# Prototype_Board_bad_routing.net
KiCad netlist of a schematic drawn in EAGLE
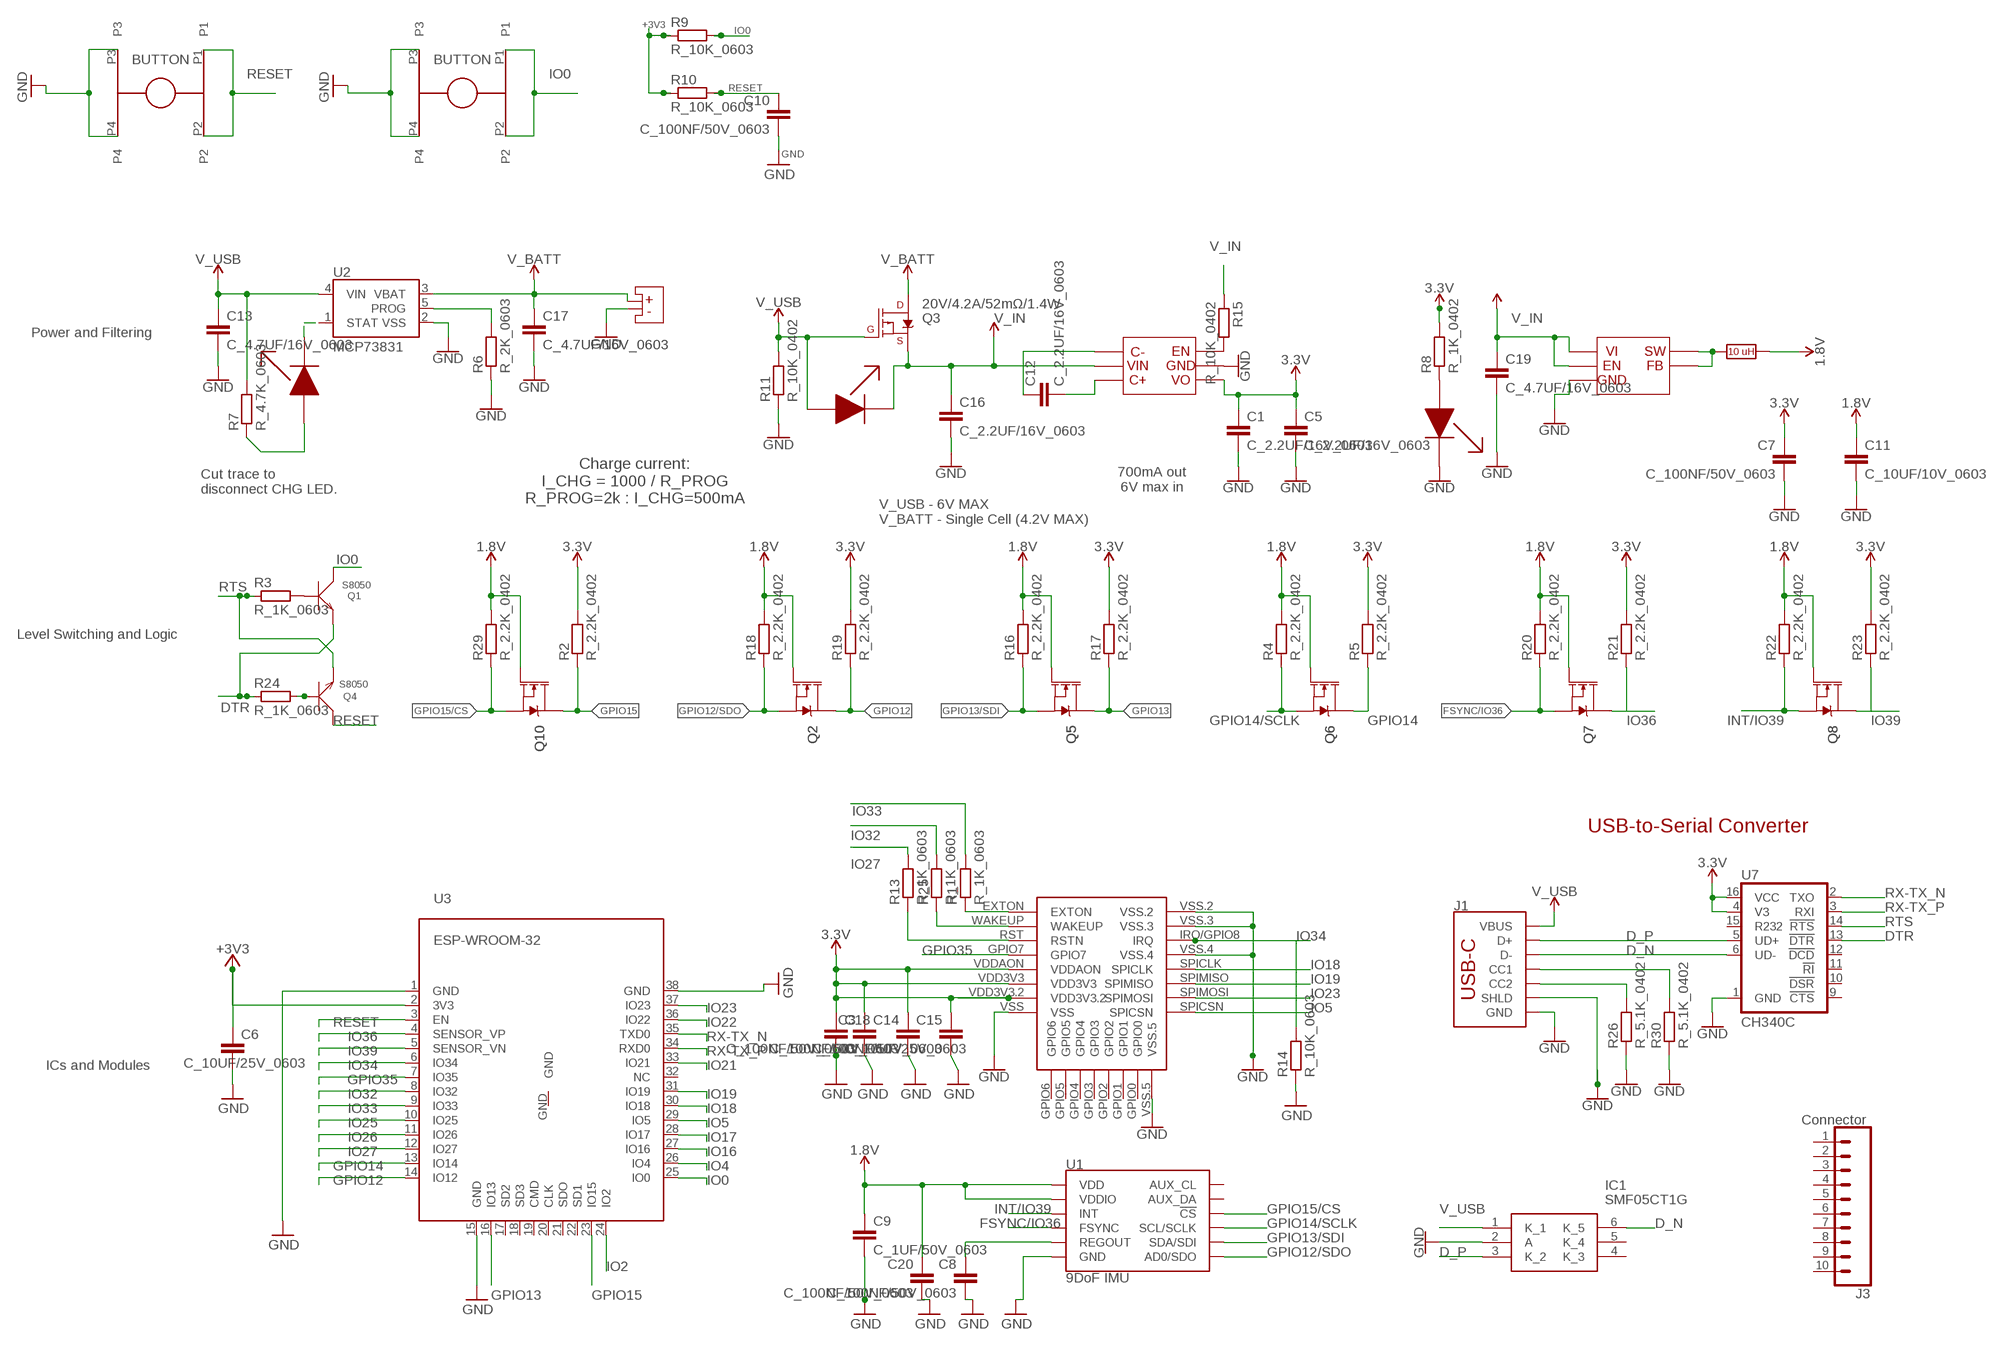
[diagram p0: schematic, sheet 1]

(export (version "E")
  (design (tool "Eeschema 10.0.6"))
  (components
    (comp (ref "C1")
      (value "C_2.2UF/16V_0603")
      (footprint "eagle-import:C0603")
      (fields (field (name "LCSC_PART") "C23630"))
      (libsource (lib "eagle-import") (part "C__06032.2UF/16V"))
    )
    (comp (ref "C3")
      (value "C_100NF/50V_0603")
      (footprint "eagle-import:C0603")
      (fields (field (name "LCSC_PART") "C14663"))
      (libsource (lib "eagle-import") (part "C__0603100NF/50V"))
    )
    (comp (ref "C5")
      (value "C_2.2UF/16V_0603")
      (footprint "eagle-import:C0603")
      (fields (field (name "LCSC_PART") "C23630"))
      (libsource (lib "eagle-import") (part "C__06032.2UF/16V"))
    )
    (comp (ref "C6")
      (value "C_10UF/25V_0603")
      (footprint "eagle-import:C0603")
      (fields (field (name "LCSC_PART") "C96446"))
      (libsource (lib "eagle-import") (part "C__060310UF/25V"))
    )
    (comp (ref "C7")
      (value "C_100NF/50V_0603")
      (footprint "eagle-import:C0603")
      (fields (field (name "LCSC_PART") "C14663"))
      (libsource (lib "eagle-import") (part "C__0603100NF/50V"))
    )
    (comp (ref "C8")
      (value "C_100NF/50V_0603")
      (footprint "eagle-import:C0603")
      (fields (field (name "LCSC_PART") "C14663"))
      (libsource (lib "eagle-import") (part "C__0603100NF/50V"))
    )
    (comp (ref "C9")
      (value "C_1UF/50V_0603")
      (footprint "eagle-import:C0603")
      (fields (field (name "LCSC_PART") "C15849"))
      (libsource (lib "eagle-import") (part "C__06031UF/50V"))
    )
    (comp (ref "C10")
      (value "C_100NF/50V_0603")
      (footprint "eagle-import:C0603")
      (fields (field (name "LCSC_PART") "C14663"))
      (libsource (lib "eagle-import") (part "C__0603100NF/50V"))
    )
    (comp (ref "C11")
      (value "C_10UF/10V_0603")
      (footprint "eagle-import:C0603")
      (fields (field (name "LCSC_PART") "C19702"))
      (libsource (lib "eagle-import") (part "C__060310UF/10V"))
    )
    (comp (ref "C12")
      (value "C_2.2UF/16V_0603")
      (footprint "eagle-import:C0603")
      (fields (field (name "LCSC_PART") "C23630"))
      (libsource (lib "eagle-import") (part "C__06032.2UF/16V"))
    )
    (comp (ref "C13")
      (value "C_4.7UF/16V_0603")
      (footprint "eagle-import:C0603")
      (fields (field (name "LCSC_PART") "C19666"))
      (libsource (lib "eagle-import") (part "C__06034.7UF/16V"))
    )
    (comp (ref "C14")
      (value "C_100NF/50V_0603")
      (footprint "eagle-import:C0603")
      (fields (field (name "LCSC_PART") "C14663"))
      (libsource (lib "eagle-import") (part "C__0603100NF/50V"))
    )
    (comp (ref "C15")
      (value "C_100NF/50V_0603")
      (footprint "eagle-import:C0603")
      (fields (field (name "LCSC_PART") "C14663"))
      (libsource (lib "eagle-import") (part "C__0603100NF/50V"))
    )
    (comp (ref "C16")
      (value "C_2.2UF/16V_0603")
      (footprint "eagle-import:C0603")
      (fields (field (name "LCSC_PART") "C23630"))
      (libsource (lib "eagle-import") (part "C__06032.2UF/16V"))
    )
    (comp (ref "C17")
      (value "C_4.7UF/16V_0603")
      (footprint "eagle-import:C0603")
      (fields (field (name "LCSC_PART") "C19666"))
      (libsource (lib "eagle-import") (part "C__06034.7UF/16V"))
    )
    (comp (ref "C18")
      (value "C_10UF/25V_0603")
      (footprint "eagle-import:C0603")
      (fields (field (name "LCSC_PART") "C96446"))
      (libsource (lib "eagle-import") (part "C__060310UF/25V"))
    )
    (comp (ref "C19")
      (value "C_4.7UF/16V_0603")
      (footprint "eagle-import:C0603")
      (fields (field (name "LCSC_PART") "C19666"))
      (libsource (lib "eagle-import") (part "C__06034.7UF/16V"))
    )
    (comp (ref "C20")
      (value "C_100NF/50V_0603")
      (footprint "eagle-import:C0603")
      (fields (field (name "LCSC_PART") "C14663"))
      (libsource (lib "eagle-import") (part "C__0603100NF/50V"))
    )
    (comp (ref "IC1")
      (value "SMF05CT1G")
      (footprint "eagle-import:SOT65P210X110-6N")
      (fields (field (name "MOUSER_PART_NUMBER") "863-SMF05CT1G"))
      (libsource (lib "eagle-import") (part "SMF05CT1G"))
    )
    (comp (ref "J1")
      (value "USB Type C")
      (footprint "eagle-import:USB-C-16P-2LAYER-PADS")
      (libsource (lib "eagle-import") (part "USB_C_2-LAYER_PADS"))
    )
    (comp (ref "J3")
      (value "Connector")
      (footprint "eagle-import:1X10")
      (libsource (lib "eagle-import") (part "CONN_10{dblquote}"))
    )
    (comp (ref "Q1")
      (value "S8050")
      (footprint "eagle-import:SOT23")
      (libsource (lib "eagle-import") (part "TRANSISTOR-NPN-SOT23"))
    )
    (comp (ref "Q2")
      (value "20V/0.2A/8MHz/1.2Ω/1Vth")
      (footprint "eagle-import:SOT-416FL")
      (libsource (lib "eagle-import") (part "MOSFET-NCH-RE1C002UN"))
    )
    (comp (ref "Q3")
      (value "20V/4.2A/52mΩ/1.4W")
      (footprint "eagle-import:SOT23-3@1")
      (libsource (lib "eagle-import") (part "MOSFET_PCH-DMG2305UX-7"))
    )
    (comp (ref "Q4")
      (value "S8050")
      (footprint "eagle-import:SOT23")
      (libsource (lib "eagle-import") (part "TRANSISTOR-NPN-SOT23"))
    )
    (comp (ref "Q5")
      (value "20V/0.2A/8MHz/1.2Ω/1Vth")
      (footprint "eagle-import:SOT-416FL")
      (libsource (lib "eagle-import") (part "MOSFET-NCH-RE1C002UN"))
    )
    (comp (ref "Q6")
      (value "20V/0.2A/8MHz/1.2Ω/1Vth")
      (footprint "eagle-import:SOT-416FL")
      (libsource (lib "eagle-import") (part "MOSFET-NCH-RE1C002UN"))
    )
    (comp (ref "Q7")
      (value "20V/0.2A/8MHz/1.2Ω/1Vth")
      (footprint "eagle-import:SOT-416FL")
      (libsource (lib "eagle-import") (part "MOSFET-NCH-RE1C002UN"))
    )
    (comp (ref "Q8")
      (value "20V/0.2A/8MHz/1.2Ω/1Vth")
      (footprint "eagle-import:SOT-416FL")
      (libsource (lib "eagle-import") (part "MOSFET-NCH-RE1C002UN"))
    )
    (comp (ref "Q10")
      (value "20V/0.2A/8MHz/1.2Ω/1Vth")
      (footprint "eagle-import:SOT-416FL")
      (libsource (lib "eagle-import") (part "MOSFET-NCH-RE1C002UN"))
    )
    (comp (ref "R1")
      (value "R_1K_0603")
      (footprint "eagle-import:R0603")
      (fields (field (name "LCSC_PART") "C21190"))
      (libsource (lib "eagle-import") (part "R__06031K"))
    )
    (comp (ref "R2")
      (value "R_2.2K_0402")
      (footprint "eagle-import:R0402")
      (fields (field (name "LCSC_PART") "C25879"))
      (libsource (lib "eagle-import") (part "R__04022.2K"))
    )
    (comp (ref "R3")
      (value "R_1K_0603")
      (footprint "eagle-import:R0603")
      (fields (field (name "LCSC_PART") "C21190"))
      (libsource (lib "eagle-import") (part "R__06031K"))
    )
    (comp (ref "R4")
      (value "R_2.2K_0402")
      (footprint "eagle-import:R0402")
      (fields (field (name "LCSC_PART") "C25879"))
      (libsource (lib "eagle-import") (part "R__04022.2K"))
    )
    (comp (ref "R5")
      (value "R_2.2K_0402")
      (footprint "eagle-import:R0402")
      (fields (field (name "LCSC_PART") "C25879"))
      (libsource (lib "eagle-import") (part "R__04022.2K"))
    )
    (comp (ref "R6")
      (value "R_2K_0603")
      (footprint "eagle-import:R0603")
      (fields (field (name "LCSC_PART") "C22975"))
      (libsource (lib "eagle-import") (part "R__06032K"))
    )
    (comp (ref "R7")
      (value "R_4.7K_0603")
      (footprint "eagle-import:R0603")
      (fields (field (name "LCSC_PART") "C23162"))
      (libsource (lib "eagle-import") (part "R__06034.7K"))
    )
    (comp (ref "R8")
      (value "R_1K_0402")
      (footprint "eagle-import:R0402")
      (fields (field (name "LCSC_PART") "C11702"))
      (libsource (lib "eagle-import") (part "R__04021K"))
    )
    (comp (ref "R9")
      (value "R_10K_0603")
      (footprint "eagle-import:R0603")
      (fields (field (name "LCSC_PART") "C25804"))
      (libsource (lib "eagle-import") (part "R__060310K"))
    )
    (comp (ref "R10")
      (value "R_10K_0603")
      (footprint "eagle-import:R0603")
      (fields (field (name "LCSC_PART") "C25804"))
      (libsource (lib "eagle-import") (part "R__060310K"))
    )
    (comp (ref "R11")
      (value "R_10K_0402")
      (footprint "eagle-import:R0402")
      (fields (field (name "LCSC_PART") "C25744"))
      (libsource (lib "eagle-import") (part "R__040210K"))
    )
    (comp (ref "R13")
      (value "R_1K_0603")
      (footprint "eagle-import:R0603")
      (fields (field (name "LCSC_PART") "C21190"))
      (libsource (lib "eagle-import") (part "R__06031K"))
    )
    (comp (ref "R14")
      (value "R_10K_0603")
      (footprint "eagle-import:R0603")
      (fields (field (name "LCSC_PART") "C25804"))
      (libsource (lib "eagle-import") (part "R__060310K"))
    )
    (comp (ref "R15")
      (value "R_10K_0402")
      (footprint "eagle-import:R0402")
      (fields (field (name "LCSC_PART") "C25744"))
      (libsource (lib "eagle-import") (part "R__040210K"))
    )
    (comp (ref "R16")
      (value "R_2.2K_0402")
      (footprint "eagle-import:R0402")
      (fields (field (name "LCSC_PART") "C25879"))
      (libsource (lib "eagle-import") (part "R__04022.2K"))
    )
    (comp (ref "R17")
      (value "R_2.2K_0402")
      (footprint "eagle-import:R0402")
      (fields (field (name "LCSC_PART") "C25879"))
      (libsource (lib "eagle-import") (part "R__04022.2K"))
    )
    (comp (ref "R18")
      (value "R_2.2K_0402")
      (footprint "eagle-import:R0402")
      (fields (field (name "LCSC_PART") "C25879"))
      (libsource (lib "eagle-import") (part "R__04022.2K"))
    )
    (comp (ref "R19")
      (value "R_2.2K_0402")
      (footprint "eagle-import:R0402")
      (fields (field (name "LCSC_PART") "C25879"))
      (libsource (lib "eagle-import") (part "R__04022.2K"))
    )
    (comp (ref "R20")
      (value "R_2.2K_0402")
      (footprint "eagle-import:R0402")
      (fields (field (name "LCSC_PART") "C25879"))
      (libsource (lib "eagle-import") (part "R__04022.2K"))
    )
    (comp (ref "R21")
      (value "R_2.2K_0402")
      (footprint "eagle-import:R0402")
      (fields (field (name "LCSC_PART") "C25879"))
      (libsource (lib "eagle-import") (part "R__04022.2K"))
    )
    (comp (ref "R22")
      (value "R_2.2K_0402")
      (footprint "eagle-import:R0402")
      (fields (field (name "LCSC_PART") "C25879"))
      (libsource (lib "eagle-import") (part "R__04022.2K"))
    )
    (comp (ref "R23")
      (value "R_2.2K_0402")
      (footprint "eagle-import:R0402")
      (fields (field (name "LCSC_PART") "C25879"))
      (libsource (lib "eagle-import") (part "R__04022.2K"))
    )
    (comp (ref "R24")
      (value "R_1K_0603")
      (footprint "eagle-import:R0603")
      (fields (field (name "LCSC_PART") "C21190"))
      (libsource (lib "eagle-import") (part "R__06031K"))
    )
    (comp (ref "R25")
      (value "R_1K_0603")
      (footprint "eagle-import:R0603")
      (fields (field (name "LCSC_PART") "C21190"))
      (libsource (lib "eagle-import") (part "R__06031K"))
    )
    (comp (ref "R26")
      (value "R_5.1K_0402")
      (footprint "eagle-import:R0402")
      (fields (field (name "LCSC_PART") "C25905"))
      (libsource (lib "eagle-import") (part "R__04025.1K"))
    )
    (comp (ref "R29")
      (value "R_2.2K_0402")
      (footprint "eagle-import:R0402")
      (fields (field (name "LCSC_PART") "C25879"))
      (libsource (lib "eagle-import") (part "R__04022.2K"))
    )
    (comp (ref "R30")
      (value "R_5.1K_0402")
      (footprint "eagle-import:R0402")
      (fields (field (name "LCSC_PART") "C25905"))
      (libsource (lib "eagle-import") (part "R__04025.1K"))
    )
    (comp (ref "U$1")
      (value "K2-6639SP-C4SC-04_C83206")
      (footprint "eagle-import:K2-6639SP-C4SC-04")
      (libsource (lib "eagle-import") (part "K2-6639SP-C4SC-04_C83206"))
    )
    (comp (ref "U$2")
      (value "MLF2012")
      (footprint "eagle-import:MLF2012")
      (libsource (lib "eagle-import") (part "MLF2012"))
    )
    (comp (ref "U$3")
      (value "K2-6639SP-C4SC-04_C83206")
      (footprint "eagle-import:K2-6639SP-C4SC-04")
      (libsource (lib "eagle-import") (part "K2-6639SP-C4SC-04_C83206"))
    )
    (comp (ref "U$4")
      (value "TPS62202DBVR")
      (footprint "eagle-import:TPS62202DBVR")
      (libsource (lib "eagle-import") (part "TPS62202DBVR"))
    )
    (comp (ref "U$5")
      (value "HE9008M6R")
      (footprint "eagle-import:HE9008M6R")
      (libsource (lib "eagle-import") (part "HE9008M6R"))
    )
    (comp (ref "U$6")
      (value "19-217/GHC-YR1S2/3T")
      (footprint "eagle-import:19-217_GHC-YR1S2_3T")
      (libsource (lib "eagle-import") (part "19-217/GHC-YR1S2/3T"))
    )
    (comp (ref "U$7")
      (value "19-217/GHC-YR1S2/3T")
      (footprint "eagle-import:19-217_GHC-YR1S2_3T")
      (libsource (lib "eagle-import") (part "19-217/GHC-YR1S2/3T"))
    )
    (comp (ref "U$8")
      (value "SM02B_PASS_TB_LF")
      (footprint "eagle-import:SM02B_PASS_TB_LF")
      (libsource (lib "eagle-import") (part "SM02B_PASS_TB_LF"))
    )
    (comp (ref "U$9")
      (value "19-217/GHC-YR1S2/3T")
      (footprint "eagle-import:19-217_GHC-YR1S2_3T")
      (libsource (lib "eagle-import") (part "19-217/GHC-YR1S2/3T"))
    )
    (comp (ref "U1")
      (value "9DoF IMU")
      (footprint "eagle-import:QFN24-3X3")
      (libsource (lib "eagle-import") (part "ICM-20948"))
    )
    (comp (ref "U2")
      (value "MCP73831")
      (footprint "eagle-import:SOT23-5")
      (libsource (lib "eagle-import") (part "MCP73831"))
    )
    (comp (ref "U3")
      (value "ESP-WROOM-32")
      (footprint "eagle-import:ESP-WROOM-32")
      (libsource (lib "eagle-import") (part "ESP-WROOM-32"))
    )
    (comp (ref "U5")
      (value "DWM1000")
      (footprint "eagle-import:DWM1000")
      (libsource (lib "eagle-import") (part "DWM1000"))
    )
    (comp (ref "U7")
      (value "CH340C")
      (footprint "eagle-import:SO016")
      (libsource (lib "eagle-import") (part "CH340C"))
    )
  )
  (nets
    (net (code "1") (name "+3V3") (class "Default")
      (node (ref "C6") (pin "1") (pinfunction "1_1") (pintype "passive"))
      (node (ref "R10") (pin "1") (pinfunction "1_1") (pintype "passive"))
      (node (ref "R9") (pin "1") (pinfunction "1_1") (pintype "passive"))
      (node (ref "U3") (pin "2") (pinfunction "3V3_2") (pintype "bidirectional"))
    )
    (net (code "2") (name "/DTR") (class "Default")
      (node (ref "Q1") (pin "2") (pinfunction "E_2") (pintype "passive"))
      (node (ref "R24") (pin "1") (pinfunction "1_1") (pintype "passive"))
      (node (ref "U7") (pin "13") (pinfunction "~{DTR}_13") (pintype "bidirectional"))
    )
    (net (code "3") (name "/D_N") (class "Default")
      (node (ref "IC1") (pin "6") (pinfunction "K_5_6") (pintype "bidirectional"))
      (node (ref "J1") (pin "A7") (pinfunction "D-_A7") (pintype "bidirectional"))
      (node (ref "J1") (pin "B7") (pinfunction "D-_B7") (pintype "bidirectional"))
      (node (ref "U7") (pin "6") (pinfunction "UD-_6") (pintype "bidirectional"))
    )
    (net (code "4") (name "/D_P") (class "Default")
      (node (ref "IC1") (pin "3") (pinfunction "K_2_3") (pintype "bidirectional"))
      (node (ref "J1") (pin "A6") (pinfunction "D+_A6") (pintype "bidirectional"))
      (node (ref "J1") (pin "B6") (pinfunction "D+_B6") (pintype "bidirectional"))
      (node (ref "U7") (pin "5") (pinfunction "UD+_5") (pintype "bidirectional"))
    )
    (net (code "5") (name "/GPIO14") (class "Default")
      (node (ref "Q6") (pin "3") (pinfunction "D_3") (pintype "bidirectional"))
      (node (ref "R5") (pin "1") (pinfunction "1_1") (pintype "passive"))
      (node (ref "U3") (pin "13") (pinfunction "IO14_13") (pintype "bidirectional"))
    )
    (net (code "6") (name "/GPIO14{slash}SCLK") (class "Default")
      (node (ref "Q6") (pin "2") (pinfunction "S_2") (pintype "bidirectional"))
      (node (ref "R4") (pin "1") (pinfunction "1_1") (pintype "passive"))
      (node (ref "U1") (pin "23") (pinfunction "SCL/SCLK_23") (pintype "bidirectional"))
    )
    (net (code "7") (name "/GPIO35") (class "Default")
      (node (ref "U3") (pin "7") (pinfunction "IO35_7") (pintype "bidirectional"))
      (node (ref "U5") (pin "GPIO7") (pinfunction "GPIO7_GPIO7") (pintype "bidirectional"))
    )
    (net (code "8") (name "/INT{slash}IO39") (class "Default")
      (node (ref "Q8") (pin "2") (pinfunction "S_2") (pintype "bidirectional"))
      (node (ref "R22") (pin "1") (pinfunction "1_1") (pintype "passive"))
      (node (ref "U1") (pin "12") (pinfunction "INT_12") (pintype "bidirectional"))
    )
    (net (code "9") (name "/IO0") (class "Default")
      (node (ref "Q1") (pin "3") (pinfunction "C_3") (pintype "passive"))
      (node (ref "R9") (pin "2") (pinfunction "2_2") (pintype "passive"))
      (node (ref "U$3") (pin "P1") (pinfunction "P1_P1") (pintype "bidirectional"))
      (node (ref "U$3") (pin "P2") (pinfunction "P2_P2") (pintype "bidirectional"))
      (node (ref "U3") (pin "25") (pinfunction "IO0_25") (pintype "bidirectional"))
    )
    (net (code "10") (name "/IO2") (class "Default")
      (node (ref "U3") (pin "24") (pinfunction "IO2_24") (pintype "bidirectional"))
    )
    (net (code "11") (name "/IO4") (class "Default")
      (node (ref "U3") (pin "26") (pinfunction "IO4_26") (pintype "bidirectional"))
    )
    (net (code "12") (name "/IO5") (class "Default")
      (node (ref "U3") (pin "29") (pinfunction "IO5_29") (pintype "bidirectional"))
      (node (ref "U5") (pin "SPICSN") (pinfunction "SPICSN_SPICSN") (pintype "bidirectional"))
    )
    (net (code "13") (name "/IO16") (class "Default")
      (node (ref "U3") (pin "27") (pinfunction "IO16_27") (pintype "bidirectional"))
    )
    (net (code "14") (name "/IO17") (class "Default")
      (node (ref "U3") (pin "28") (pinfunction "IO17_28") (pintype "bidirectional"))
    )
    (net (code "15") (name "/IO18") (class "Default")
      (node (ref "U3") (pin "30") (pinfunction "IO18_30") (pintype "bidirectional"))
      (node (ref "U5") (pin "SPICLK") (pinfunction "SPICLK_SPICLK") (pintype "bidirectional"))
    )
    (net (code "16") (name "/IO19") (class "Default")
      (node (ref "U3") (pin "31") (pinfunction "IO19_31") (pintype "bidirectional"))
      (node (ref "U5") (pin "SPIMISO") (pinfunction "SPIMISO_SPIMISO") (pintype "bidirectional"))
    )
    (net (code "17") (name "/IO21") (class "Default")
      (node (ref "U3") (pin "33") (pinfunction "IO21_33") (pintype "bidirectional"))
    )
    (net (code "18") (name "/IO22") (class "Default")
      (node (ref "U3") (pin "36") (pinfunction "IO22_36") (pintype "bidirectional"))
    )
    (net (code "19") (name "/IO23") (class "Default")
      (node (ref "U3") (pin "37") (pinfunction "IO23_37") (pintype "bidirectional"))
      (node (ref "U5") (pin "SPIMOSI") (pinfunction "SPIMOSI_SPIMOSI") (pintype "bidirectional"))
    )
    (net (code "20") (name "/IO25") (class "Default")
      (node (ref "U3") (pin "10") (pinfunction "IO25_10") (pintype "bidirectional"))
    )
    (net (code "21") (name "/IO26") (class "Default")
      (node (ref "U3") (pin "11") (pinfunction "IO26_11") (pintype "bidirectional"))
    )
    (net (code "22") (name "/IO27") (class "Default")
      (node (ref "R13") (pin "2") (pinfunction "2_2") (pintype "passive"))
      (node (ref "U3") (pin "12") (pinfunction "IO27_12") (pintype "bidirectional"))
    )
    (net (code "23") (name "/IO32") (class "Default")
      (node (ref "R25") (pin "2") (pinfunction "2_2") (pintype "passive"))
      (node (ref "U3") (pin "8") (pinfunction "IO32_8") (pintype "bidirectional"))
    )
    (net (code "24") (name "/IO33") (class "Default")
      (node (ref "R1") (pin "2") (pinfunction "2_2") (pintype "passive"))
      (node (ref "U3") (pin "9") (pinfunction "IO33_9") (pintype "bidirectional"))
    )
    (net (code "25") (name "/IO34") (class "Default")
      (node (ref "R14") (pin "2") (pinfunction "2_2") (pintype "passive"))
      (node (ref "U3") (pin "6") (pinfunction "IO34_6") (pintype "bidirectional"))
      (node (ref "U5") (pin "IRQ/GPIO8") (pinfunction "IRQ_IRQ/GPIO8") (pintype "bidirectional"))
    )
    (net (code "26") (name "/IO36") (class "Default")
      (node (ref "Q7") (pin "3") (pinfunction "D_3") (pintype "bidirectional"))
      (node (ref "R21") (pin "1") (pinfunction "1_1") (pintype "passive"))
      (node (ref "U3") (pin "4") (pinfunction "SENSOR_VP_4") (pintype "bidirectional"))
    )
    (net (code "27") (name "/IO39") (class "Default")
      (node (ref "Q8") (pin "3") (pinfunction "D_3") (pintype "bidirectional"))
      (node (ref "R23") (pin "1") (pinfunction "1_1") (pintype "passive"))
      (node (ref "U3") (pin "5") (pinfunction "SENSOR_VN_5") (pintype "bidirectional"))
    )
    (net (code "28") (name "/RESET") (class "Default")
      (node (ref "C10") (pin "1") (pinfunction "1_1") (pintype "passive"))
      (node (ref "Q4") (pin "3") (pinfunction "C_3") (pintype "passive"))
      (node (ref "R10") (pin "2") (pinfunction "2_2") (pintype "passive"))
      (node (ref "U$1") (pin "P1") (pinfunction "P1_P1") (pintype "bidirectional"))
      (node (ref "U$1") (pin "P2") (pinfunction "P2_P2") (pintype "bidirectional"))
      (node (ref "U3") (pin "3") (pinfunction "EN_3") (pintype "bidirectional"))
    )
    (net (code "29") (name "/RTS") (class "Default")
      (node (ref "Q4") (pin "2") (pinfunction "E_2") (pintype "passive"))
      (node (ref "R3") (pin "1") (pinfunction "1_1") (pintype "passive"))
      (node (ref "U7") (pin "14") (pinfunction "~{RTS}_14") (pintype "bidirectional"))
    )
    (net (code "30") (name "/RX-TX_N") (class "Default")
      (node (ref "U3") (pin "35") (pinfunction "TXD0_35") (pintype "bidirectional"))
      (node (ref "U7") (pin "2") (pinfunction "TXO_2") (pintype "bidirectional"))
    )
    (net (code "31") (name "/RX-TX_P") (class "Default")
      (node (ref "U3") (pin "34") (pinfunction "RXD0_34") (pintype "bidirectional"))
      (node (ref "U7") (pin "3") (pinfunction "RXI_3") (pintype "bidirectional"))
    )
    (net (code "32") (name "1.8V") (class "Default")
      (node (ref "C11") (pin "1") (pinfunction "1_1") (pintype "passive"))
      (node (ref "C20") (pin "1") (pinfunction "1_1") (pintype "passive"))
      (node (ref "C9") (pin "1") (pinfunction "1_1") (pintype "passive"))
      (node (ref "Q10") (pin "1") (pinfunction "G_1") (pintype "bidirectional"))
      (node (ref "Q2") (pin "1") (pinfunction "G_1") (pintype "bidirectional"))
      (node (ref "Q5") (pin "1") (pinfunction "G_1") (pintype "bidirectional"))
      (node (ref "Q6") (pin "1") (pinfunction "G_1") (pintype "bidirectional"))
      (node (ref "Q7") (pin "1") (pinfunction "G_1") (pintype "bidirectional"))
      (node (ref "Q8") (pin "1") (pinfunction "G_1") (pintype "bidirectional"))
      (node (ref "R16") (pin "2") (pinfunction "2_2") (pintype "passive"))
      (node (ref "R18") (pin "2") (pinfunction "2_2") (pintype "passive"))
      (node (ref "R20") (pin "2") (pinfunction "2_2") (pintype "passive"))
      (node (ref "R22") (pin "2") (pinfunction "2_2") (pintype "passive"))
      (node (ref "R29") (pin "2") (pinfunction "2_2") (pintype "passive"))
      (node (ref "R4") (pin "2") (pinfunction "2_2") (pintype "passive"))
      (node (ref "U$2") (pin "2") (pinfunction "P$2_2") (pintype "bidirectional"))
      (node (ref "U1") (pin "13") (pinfunction "VDD_13") (pintype "bidirectional"))
      (node (ref "U1") (pin "8") (pinfunction "VDDIO_8") (pintype "bidirectional"))
    )
    (net (code "33") (name "3.3V") (class "Default")
      (node (ref "C1") (pin "1") (pinfunction "1_1") (pintype "passive"))
      (node (ref "C14") (pin "1") (pinfunction "1_1") (pintype "passive"))
      (node (ref "C15") (pin "1") (pinfunction "1_1") (pintype "passive"))
      (node (ref "C18") (pin "1") (pinfunction "1_1") (pintype "passive"))
      (node (ref "C3") (pin "1") (pinfunction "1_1") (pintype "passive"))
      (node (ref "C5") (pin "1") (pinfunction "1_1") (pintype "passive"))
      (node (ref "C7") (pin "1") (pinfunction "1_1") (pintype "passive"))
      (node (ref "R17") (pin "2") (pinfunction "2_2") (pintype "passive"))
      (node (ref "R19") (pin "2") (pinfunction "2_2") (pintype "passive"))
      (node (ref "R2") (pin "2") (pinfunction "2_2") (pintype "passive"))
      (node (ref "R21") (pin "2") (pinfunction "2_2") (pintype "passive"))
      (node (ref "R23") (pin "2") (pinfunction "2_2") (pintype "passive"))
      (node (ref "R5") (pin "2") (pinfunction "2_2") (pintype "passive"))
      (node (ref "R8") (pin "2") (pinfunction "2_2") (pintype "passive"))
      (node (ref "U$5") (pin "VOUT") (pinfunction "VO_VOUT") (pintype "bidirectional"))
      (node (ref "U5") (pin "VDD3V3") (pinfunction "VDD3V3_VDD3V3") (pintype "bidirectional"))
      (node (ref "U5") (pin "VDD3V3.2") (pinfunction "VDD3V3.2_VDD3V3.2") (pintype "bidirectional"))
      (node (ref "U5") (pin "VDDAON") (pinfunction "VDDAON_VDDAON") (pintype "bidirectional"))
      (node (ref "U7") (pin "16") (pinfunction "VCC_16") (pintype "bidirectional"))
      (node (ref "U7") (pin "4") (pinfunction "V3_4") (pintype "bidirectional"))
    )
    (net (code "34") (name "FSYNC{slash}IO36") (class "Default")
      (node (ref "Q7") (pin "2") (pinfunction "S_2") (pintype "bidirectional"))
      (node (ref "R20") (pin "1") (pinfunction "1_1") (pintype "passive"))
      (node (ref "U1") (pin "11") (pinfunction "FSYNC_11") (pintype "bidirectional"))
    )
    (net (code "35") (name "GND") (class "Default")
      (node (ref "C1") (pin "2") (pinfunction "2_2") (pintype "passive"))
      (node (ref "C10") (pin "2") (pinfunction "2_2") (pintype "passive"))
      (node (ref "C11") (pin "2") (pinfunction "2_2") (pintype "passive"))
      (node (ref "C13") (pin "2") (pinfunction "2_2") (pintype "passive"))
      (node (ref "C14") (pin "2") (pinfunction "2_2") (pintype "passive"))
      (node (ref "C15") (pin "2") (pinfunction "2_2") (pintype "passive"))
      (node (ref "C16") (pin "2") (pinfunction "2_2") (pintype "passive"))
      (node (ref "C17") (pin "2") (pinfunction "2_2") (pintype "passive"))
      (node (ref "C18") (pin "2") (pinfunction "2_2") (pintype "passive"))
      (node (ref "C19") (pin "2") (pinfunction "2_2") (pintype "passive"))
      (node (ref "C20") (pin "2") (pinfunction "2_2") (pintype "passive"))
      (node (ref "C3") (pin "2") (pinfunction "2_2") (pintype "passive"))
      (node (ref "C5") (pin "2") (pinfunction "2_2") (pintype "passive"))
      (node (ref "C6") (pin "2") (pinfunction "2_2") (pintype "passive"))
      (node (ref "C7") (pin "2") (pinfunction "2_2") (pintype "passive"))
      (node (ref "C8") (pin "2") (pinfunction "2_2") (pintype "passive"))
      (node (ref "C9") (pin "2") (pinfunction "2_2") (pintype "passive"))
      (node (ref "IC1") (pin "2") (pinfunction "A_2") (pintype "bidirectional"))
      (node (ref "J1") (pin "GND") (pinfunction "GND_GND") (pintype "bidirectional"))
      (node (ref "J1") (pin "GND2") (pinfunction "GND_GND2") (pintype "bidirectional"))
      (node (ref "J1") (pin "SHLD1") (pinfunction "SHLD_SHLD1") (pintype "bidirectional"))
      (node (ref "J1") (pin "SHLD2") (pinfunction "SHLD_SHLD2") (pintype "bidirectional"))
      (node (ref "J1") (pin "SHLD3") (pinfunction "SHLD_SHLD3") (pintype "bidirectional"))
      (node (ref "J1") (pin "SHLD4") (pinfunction "SHLD_SHLD4") (pintype "bidirectional"))
      (node (ref "R11") (pin "1") (pinfunction "1_1") (pintype "passive"))
      (node (ref "R14") (pin "1") (pinfunction "1_1") (pintype "passive"))
      (node (ref "R26") (pin "1") (pinfunction "1_1") (pintype "passive"))
      (node (ref "R30") (pin "1") (pinfunction "1_1") (pintype "passive"))
      (node (ref "R6") (pin "1") (pinfunction "1_1") (pintype "passive"))
      (node (ref "U$1") (pin "P3") (pinfunction "P3_P3") (pintype "bidirectional"))
      (node (ref "U$1") (pin "P4") (pinfunction "P4_P4") (pintype "bidirectional"))
      (node (ref "U$3") (pin "P3") (pinfunction "P3_P3") (pintype "bidirectional"))
      (node (ref "U$3") (pin "P4") (pinfunction "P4_P4") (pintype "bidirectional"))
      (node (ref "U$4") (pin "2") (pinfunction "GND_2") (pintype "bidirectional"))
      (node (ref "U$5") (pin "GND") (pinfunction "GND_GND") (pintype "bidirectional"))
      (node (ref "U$8") (pin "3") (pinfunction "-_3") (pintype "bidirectional"))
      (node (ref "U$9") (pin "2") (pinfunction "2_2") (pintype "bidirectional"))
      (node (ref "U1") (pin "18") (pinfunction "GND_18") (pintype "bidirectional"))
      (node (ref "U1") (pin "20") (pinfunction "GND_20") (pintype "bidirectional"))
      (node (ref "U2") (pin "2") (pinfunction "VSS_2") (pintype "power_in"))
      (node (ref "U3") (pin "1") (pinfunction "GND_1") (pintype "bidirectional"))
      (node (ref "U3") (pin "15") (pinfunction "GND_15") (pintype "bidirectional"))
      (node (ref "U3") (pin "38") (pinfunction "GND_38") (pintype "bidirectional"))
      (node (ref "U5") (pin "VSS") (pinfunction "VSS_VSS") (pintype "bidirectional"))
      (node (ref "U5") (pin "VSS.2") (pinfunction "VSS.2_VSS.2") (pintype "bidirectional"))
      (node (ref "U5") (pin "VSS.3") (pinfunction "VSS.3_VSS.3") (pintype "bidirectional"))
      (node (ref "U5") (pin "VSS.4") (pinfunction "VSS.4_VSS.4") (pintype "bidirectional"))
      (node (ref "U5") (pin "VSS.5") (pinfunction "VSS.5_VSS.5") (pintype "bidirectional"))
      (node (ref "U7") (pin "1") (pinfunction "GND_1") (pintype "bidirectional"))
    )
    (net (code "36") (name "GPIO12") (class "Default")
      (node (ref "Q2") (pin "3") (pinfunction "D_3") (pintype "bidirectional"))
      (node (ref "R19") (pin "1") (pinfunction "1_1") (pintype "passive"))
      (node (ref "U3") (pin "14") (pinfunction "IO12_14") (pintype "bidirectional"))
    )
    (net (code "37") (name "GPIO12{slash}SDO") (class "Default")
      (node (ref "Q2") (pin "2") (pinfunction "S_2") (pintype "bidirectional"))
      (node (ref "R18") (pin "1") (pinfunction "1_1") (pintype "passive"))
      (node (ref "U1") (pin "9") (pinfunction "AD0/SDO_9") (pintype "bidirectional"))
    )
    (net (code "38") (name "GPIO13") (class "Default")
      (node (ref "Q5") (pin "3") (pinfunction "D_3") (pintype "bidirectional"))
      (node (ref "R17") (pin "1") (pinfunction "1_1") (pintype "passive"))
      (node (ref "U3") (pin "16") (pinfunction "IO13_16") (pintype "bidirectional"))
    )
    (net (code "39") (name "GPIO13{slash}SDI") (class "Default")
      (node (ref "Q5") (pin "2") (pinfunction "S_2") (pintype "bidirectional"))
      (node (ref "R16") (pin "1") (pinfunction "1_1") (pintype "passive"))
      (node (ref "U1") (pin "24") (pinfunction "SDA/SDI_24") (pintype "bidirectional"))
    )
    (net (code "40") (name "GPIO15") (class "Default")
      (node (ref "Q10") (pin "3") (pinfunction "D_3") (pintype "bidirectional"))
      (node (ref "R2") (pin "1") (pinfunction "1_1") (pintype "passive"))
      (node (ref "U3") (pin "23") (pinfunction "IO15_23") (pintype "bidirectional"))
    )
    (net (code "41") (name "GPIO15{slash}CS") (class "Default")
      (node (ref "Q10") (pin "2") (pinfunction "S_2") (pintype "bidirectional"))
      (node (ref "R29") (pin "1") (pinfunction "1_1") (pintype "passive"))
      (node (ref "U1") (pin "22") (pinfunction "~{CS}_22") (pintype "bidirectional"))
    )
    (net (code "42") (name "Net-(C12-Pad1)") (class "Default")
      (node (ref "C12") (pin "1") (pinfunction "1_1") (pintype "passive"))
      (node (ref "U$5") (pin "C-") (pinfunction "C-_C-") (pintype "bidirectional"))
    )
    (net (code "43") (name "Net-(C12-Pad2)") (class "Default")
      (node (ref "C12") (pin "2") (pinfunction "2_2") (pintype "passive"))
      (node (ref "U$5") (pin "C+") (pinfunction "C+_C+") (pintype "bidirectional"))
    )
    (net (code "44") (name "Net-(J1-CC1)") (class "Default")
      (node (ref "J1") (pin "A5") (pinfunction "CC1_A5") (pintype "bidirectional"))
      (node (ref "R30") (pin "2") (pinfunction "2_2") (pintype "passive"))
    )
    (net (code "45") (name "Net-(J1-CC2)") (class "Default")
      (node (ref "J1") (pin "B5") (pinfunction "CC2_B5") (pintype "bidirectional"))
      (node (ref "R26") (pin "2") (pinfunction "2_2") (pintype "passive"))
    )
    (net (code "46") (name "Net-(Q1-B)") (class "Default")
      (node (ref "Q1") (pin "1") (pinfunction "B_1") (pintype "passive"))
      (node (ref "R3") (pin "2") (pinfunction "2_2") (pintype "passive"))
    )
    (net (code "47") (name "Net-(Q4-B)") (class "Default")
      (node (ref "Q4") (pin "1") (pinfunction "B_1") (pintype "passive"))
      (node (ref "R24") (pin "2") (pinfunction "2_2") (pintype "passive"))
    )
    (net (code "48") (name "Net-(R1-Pad1)") (class "Default")
      (node (ref "R1") (pin "1") (pinfunction "1_1") (pintype "passive"))
      (node (ref "U5") (pin "EXTON") (pinfunction "EXTON_EXTON") (pintype "bidirectional"))
    )
    (net (code "49") (name "Net-(R7-Pad1)") (class "Default")
      (node (ref "R7") (pin "1") (pinfunction "1_1") (pintype "passive"))
      (node (ref "U$6") (pin "1") (pinfunction "1_1") (pintype "bidirectional"))
    )
    (net (code "50") (name "Net-(R8-Pad1)") (class "Default")
      (node (ref "R8") (pin "1") (pinfunction "1_1") (pintype "passive"))
      (node (ref "U$9") (pin "1") (pinfunction "1_1") (pintype "bidirectional"))
    )
    (net (code "51") (name "Net-(R15-Pad2)") (class "Default")
      (node (ref "R15") (pin "2") (pinfunction "2_2") (pintype "passive"))
      (node (ref "U$5") (pin "EN") (pinfunction "EN_EN") (pintype "bidirectional"))
    )
    (net (code "52") (name "Net-(R25-Pad1)") (class "Default")
      (node (ref "R25") (pin "1") (pinfunction "1_1") (pintype "passive"))
      (node (ref "U5") (pin "WAKEUP") (pinfunction "WAKEUP_WAKEUP") (pintype "bidirectional"))
    )
    (net (code "53") (name "Net-(U$2-P$1)") (class "Default")
      (node (ref "U$2") (pin "1") (pinfunction "P$1_1") (pintype "bidirectional"))
      (node (ref "U$4") (pin "4") (pinfunction "FB_4") (pintype "bidirectional"))
      (node (ref "U$4") (pin "5") (pinfunction "SW_5") (pintype "bidirectional"))
    )
    (net (code "54") (name "Net-(U1-REGOUT)") (class "Default")
      (node (ref "C8") (pin "1") (pinfunction "1_1") (pintype "passive"))
      (node (ref "U1") (pin "10") (pinfunction "REGOUT_10") (pintype "bidirectional"))
    )
    (net (code "55") (name "Net-(U2-PROG)") (class "Default")
      (node (ref "R6") (pin "2") (pinfunction "2_2") (pintype "passive"))
      (node (ref "U2") (pin "5") (pinfunction "PROG_5") (pintype "input"))
    )
    (net (code "56") (name "Net-(U2-STAT)") (class "Default")
      (node (ref "U$6") (pin "2") (pinfunction "2_2") (pintype "bidirectional"))
      (node (ref "U2") (pin "1") (pinfunction "STAT_1") (pintype "output"))
    )
    (net (code "57") (name "Net-(U5-RSTN)") (class "Default")
      (node (ref "R13") (pin "1") (pinfunction "1_1") (pintype "passive"))
      (node (ref "U5") (pin "RST") (pinfunction "RSTN_RST") (pintype "bidirectional"))
    )
    (net (code "58") (name "VIN") (class "Default")
      (node (ref "C16") (pin "1") (pinfunction "1_1") (pintype "passive"))
      (node (ref "C19") (pin "1") (pinfunction "1_1") (pintype "passive"))
      (node (ref "Q3") (pin "2") (pinfunction "S_2") (pintype "bidirectional"))
      (node (ref "R15") (pin "1") (pinfunction "1_1") (pintype "passive"))
      (node (ref "U$4") (pin "1") (pinfunction "VI_1") (pintype "bidirectional"))
      (node (ref "U$4") (pin "3") (pinfunction "EN_3") (pintype "bidirectional"))
      (node (ref "U$5") (pin "VIN") (pinfunction "VIN_VIN") (pintype "bidirectional"))
      (node (ref "U$7") (pin "2") (pinfunction "2_2") (pintype "bidirectional"))
    )
    (net (code "59") (name "V_BATT") (class "Default")
      (node (ref "C17") (pin "1") (pinfunction "1_1") (pintype "passive"))
      (node (ref "Q3") (pin "3") (pinfunction "D_3") (pintype "bidirectional"))
      (node (ref "U$8") (pin "4") (pinfunction "+_4") (pintype "bidirectional"))
      (node (ref "U2") (pin "3") (pinfunction "VBAT_3") (pintype "power_in"))
    )
    (net (code "60") (name "V_USB") (class "Default")
      (node (ref "C13") (pin "1") (pinfunction "1_1") (pintype "passive"))
      (node (ref "IC1") (pin "1") (pinfunction "K_1_1") (pintype "bidirectional"))
      (node (ref "J1") (pin "VBUS1") (pinfunction "VBUS_VBUS1") (pintype "bidirectional"))
      (node (ref "J1") (pin "VBUS2") (pinfunction "VBUS_VBUS2") (pintype "bidirectional"))
      (node (ref "Q3") (pin "1") (pinfunction "G_1") (pintype "bidirectional"))
      (node (ref "R11") (pin "2") (pinfunction "2_2") (pintype "passive"))
      (node (ref "R7") (pin "2") (pinfunction "2_2") (pintype "passive"))
      (node (ref "U$7") (pin "1") (pinfunction "1_1") (pintype "bidirectional"))
      (node (ref "U2") (pin "4") (pinfunction "VIN_4") (pintype "power_in"))
    )
    (net (code "61") (name "unconnected-(IC1-K_3-Pad4)") (class "Default")
      (node (ref "IC1") (pin "4") (pinfunction "K_3_4") (pintype "bidirectional"))
    )
    (net (code "62") (name "unconnected-(IC1-K_4-Pad5)") (class "Default")
      (node (ref "IC1") (pin "5") (pinfunction "K_4_5") (pintype "bidirectional"))
    )
    (net (code "63") (name "unconnected-(J3-Pad1)") (class "Default")
      (node (ref "J3") (pin "1") (pinfunction "1_1") (pintype "passive"))
    )
    (net (code "64") (name "unconnected-(J3-Pad2)") (class "Default")
      (node (ref "J3") (pin "2") (pinfunction "2_2") (pintype "passive"))
    )
    (net (code "65") (name "unconnected-(J3-Pad3)") (class "Default")
      (node (ref "J3") (pin "3") (pinfunction "3_3") (pintype "passive"))
    )
    (net (code "66") (name "unconnected-(J3-Pad4)") (class "Default")
      (node (ref "J3") (pin "4") (pinfunction "4_4") (pintype "passive"))
    )
    (net (code "67") (name "unconnected-(J3-Pad5)") (class "Default")
      (node (ref "J3") (pin "5") (pinfunction "5_5") (pintype "passive"))
    )
    (net (code "68") (name "unconnected-(J3-Pad6)") (class "Default")
      (node (ref "J3") (pin "6") (pinfunction "6_6") (pintype "passive"))
    )
    (net (code "69") (name "unconnected-(J3-Pad7)") (class "Default")
      (node (ref "J3") (pin "7") (pinfunction "7_7") (pintype "passive"))
    )
    (net (code "70") (name "unconnected-(J3-Pad8)") (class "Default")
      (node (ref "J3") (pin "8") (pinfunction "8_8") (pintype "passive"))
    )
    (net (code "71") (name "unconnected-(J3-Pad9)") (class "Default")
      (node (ref "J3") (pin "9") (pinfunction "9_9") (pintype "passive"))
    )
    (net (code "72") (name "unconnected-(J3-Pad10)") (class "Default")
      (node (ref "J3") (pin "10") (pinfunction "10_10") (pintype "passive"))
    )
    (net (code "73") (name "unconnected-(U1-AUX_CL-Pad7)") (class "Default")
      (node (ref "U1") (pin "7") (pinfunction "AUX_CL_7") (pintype "bidirectional"))
    )
    (net (code "74") (name "unconnected-(U1-AUX_DA-Pad21)") (class "Default")
      (node (ref "U1") (pin "21") (pinfunction "AUX_DA_21") (pintype "bidirectional"))
    )
    (net (code "75") (name "unconnected-(U3-CLK-Pad20)") (class "Default")
      (node (ref "U3") (pin "20") (pinfunction "CLK_20") (pintype "bidirectional"))
    )
    (net (code "76") (name "unconnected-(U3-CMD-Pad19)") (class "Default")
      (node (ref "U3") (pin "19") (pinfunction "CMD_19") (pintype "bidirectional"))
    )
    (net (code "77") (name "unconnected-(U3-NC-Pad32)") (class "Default")
      (node (ref "U3") (pin "32") (pinfunction "NC_32") (pintype "bidirectional"))
    )
    (net (code "78") (name "unconnected-(U3-PadGND)") (class "Default")
      (node (ref "U3") (pin "GND") (pinfunction "GND_GND") (pintype "bidirectional"))
    )
    (net (code "79") (name "unconnected-(U3-SD1-Pad22)") (class "Default")
      (node (ref "U3") (pin "22") (pinfunction "SD1_22") (pintype "bidirectional"))
    )
    (net (code "80") (name "unconnected-(U3-SD2-Pad17)") (class "Default")
      (node (ref "U3") (pin "17") (pinfunction "SD2_17") (pintype "bidirectional"))
    )
    (net (code "81") (name "unconnected-(U3-SD3-Pad18)") (class "Default")
      (node (ref "U3") (pin "18") (pinfunction "SD3_18") (pintype "bidirectional"))
    )
    (net (code "82") (name "unconnected-(U3-SDO-Pad21)") (class "Default")
      (node (ref "U3") (pin "21") (pinfunction "SDO_21") (pintype "bidirectional"))
    )
    (net (code "83") (name "unconnected-(U5-PadGPIO0)") (class "Default")
      (node (ref "U5") (pin "GPIO0") (pinfunction "GPIO0_GPIO0") (pintype "bidirectional"))
    )
    (net (code "84") (name "unconnected-(U5-PadGPIO1)") (class "Default")
      (node (ref "U5") (pin "GPIO1") (pinfunction "GPIO1_GPIO1") (pintype "bidirectional"))
    )
    (net (code "85") (name "unconnected-(U5-PadGPIO2)") (class "Default")
      (node (ref "U5") (pin "GPIO2") (pinfunction "GPIO2_GPIO2") (pintype "bidirectional"))
    )
    (net (code "86") (name "unconnected-(U5-PadGPIO3)") (class "Default")
      (node (ref "U5") (pin "GPIO3") (pinfunction "GPIO3_GPIO3") (pintype "bidirectional"))
    )
    (net (code "87") (name "unconnected-(U5-PadGPIO4)") (class "Default")
      (node (ref "U5") (pin "GPIO4") (pinfunction "GPIO4_GPIO4") (pintype "bidirectional"))
    )
    (net (code "88") (name "unconnected-(U5-PadGPIO5)") (class "Default")
      (node (ref "U5") (pin "GPIO5") (pinfunction "GPIO5_GPIO5") (pintype "bidirectional"))
    )
    (net (code "89") (name "unconnected-(U5-PadGPIO6)") (class "Default")
      (node (ref "U5") (pin "GPIO6") (pinfunction "GPIO6_GPIO6") (pintype "bidirectional"))
    )
    (net (code "90") (name "unconnected-(U7-R232-Pad15)") (class "Default")
      (node (ref "U7") (pin "15") (pinfunction "R232_15") (pintype "bidirectional"))
    )
    (net (code "91") (name "unconnected-(U7-~{CTS}-Pad9)") (class "Default")
      (node (ref "U7") (pin "9") (pinfunction "~{CTS}_9") (pintype "bidirectional"))
    )
    (net (code "92") (name "unconnected-(U7-~{DCD}-Pad12)") (class "Default")
      (node (ref "U7") (pin "12") (pinfunction "~{DCD}_12") (pintype "bidirectional"))
    )
    (net (code "93") (name "unconnected-(U7-~{DSR}-Pad10)") (class "Default")
      (node (ref "U7") (pin "10") (pinfunction "~{DSR}_10") (pintype "bidirectional"))
    )
    (net (code "94") (name "unconnected-(U7-~{RI}-Pad11)") (class "Default")
      (node (ref "U7") (pin "11") (pinfunction "~{RI}_11") (pintype "bidirectional"))
    )
  )
)
